# PV_power_board_0_1.net
KiCad netlist of a schematic drawn in EAGLE
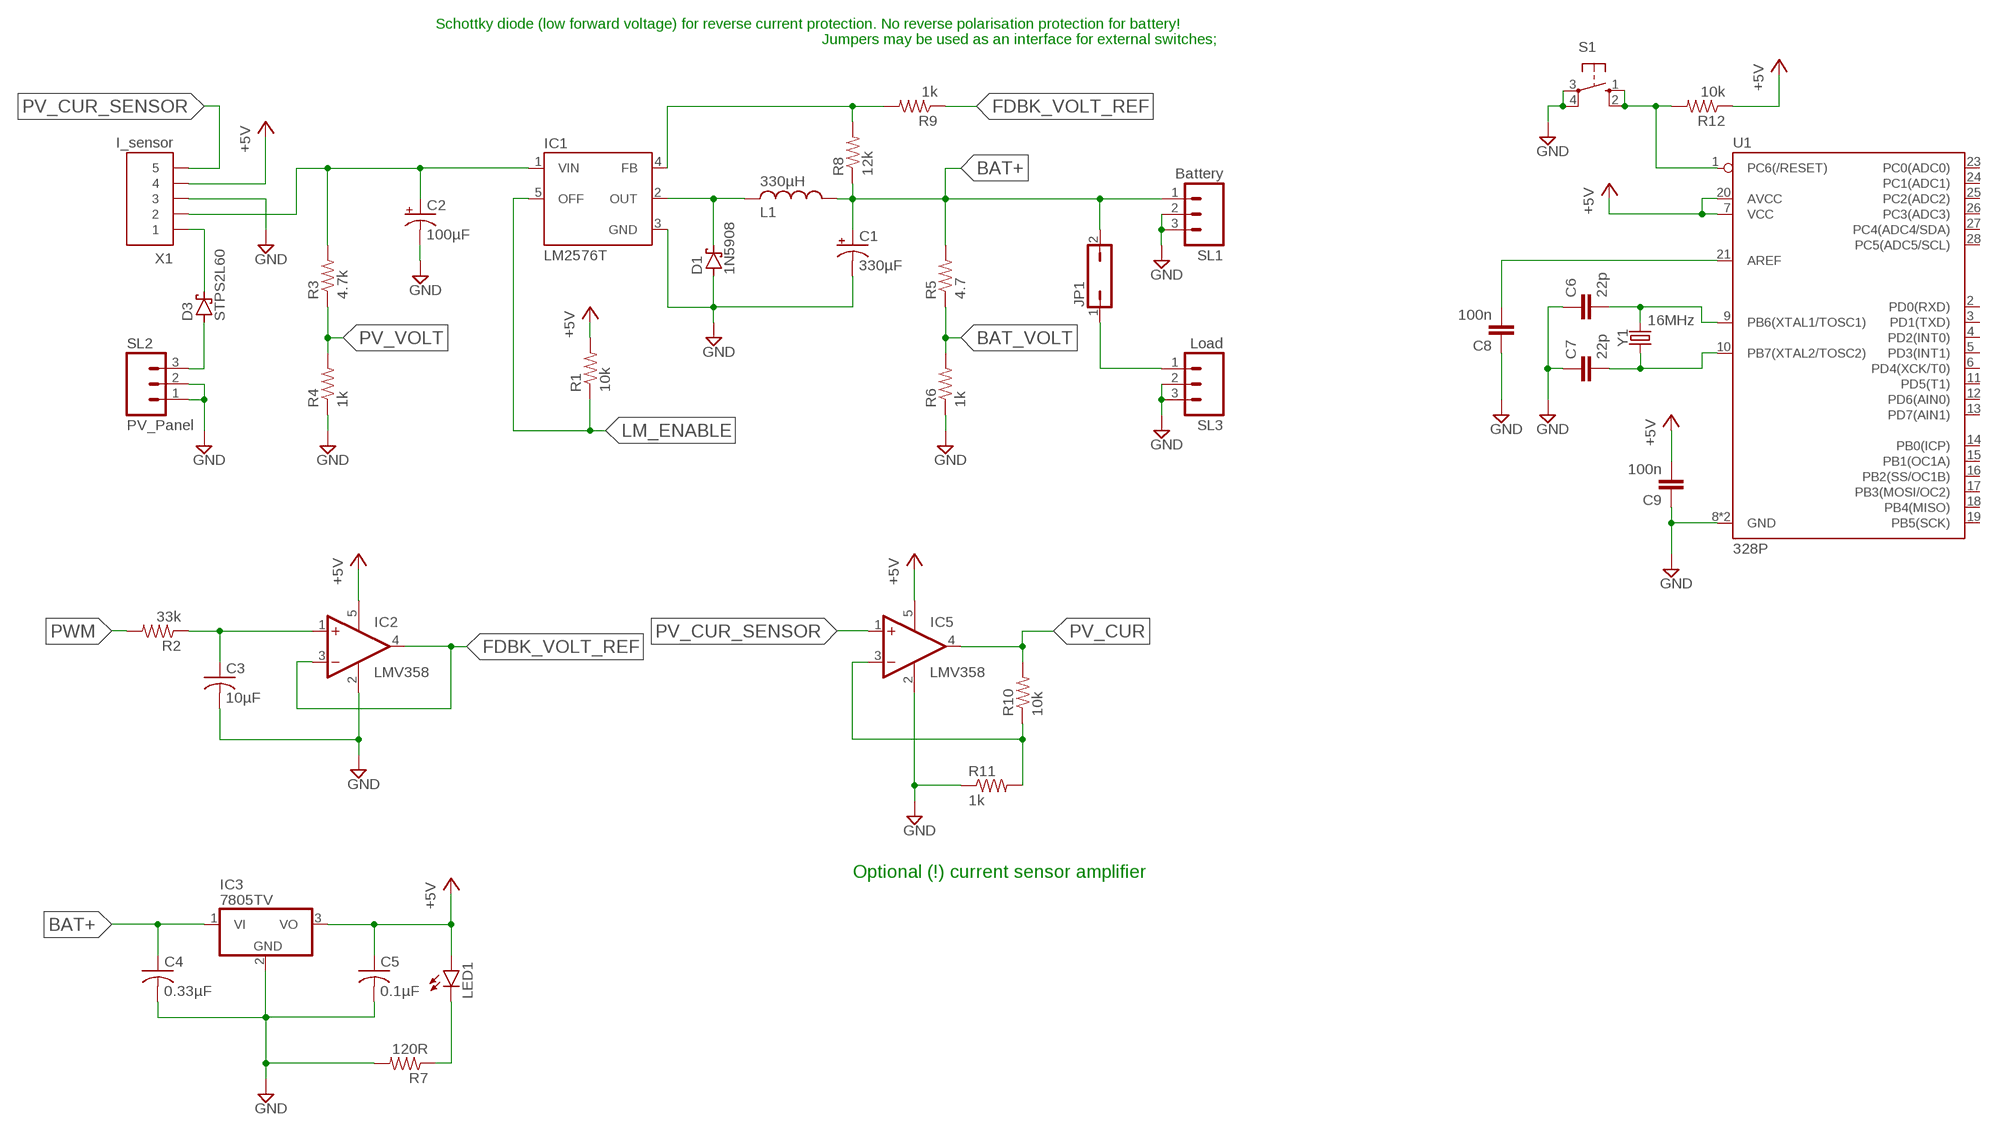
[diagram p0: schematic, sheet 1]

(export (version "E")
  (design (tool "Eeschema 10.0.6"))
  (components
    (comp (ref "C1")
      (value "330µF")
      (footprint "eagle-import:E3,5-8")
      (libsource (lib "eagle-import") (part "CPOL-USE3.5-8"))
    )
    (comp (ref "C2")
      (value "100µF")
      (footprint "eagle-import:E3,5-8")
      (libsource (lib "eagle-import") (part "CPOL-USE3.5-8"))
    )
    (comp (ref "C3")
      (value "10µF")
      (footprint "eagle-import:C025-025X050")
      (libsource (lib "eagle-import") (part "C-US025-025X050"))
    )
    (comp (ref "C4")
      (value "0.33µF")
      (footprint "eagle-import:C025-025X050")
      (libsource (lib "eagle-import") (part "C-US025-025X050"))
    )
    (comp (ref "C5")
      (value "0.1µF")
      (footprint "eagle-import:C025-025X050")
      (libsource (lib "eagle-import") (part "C-US025-025X050"))
    )
    (comp (ref "C6")
      (value "22p")
      (footprint "eagle-import:C2.5-2")
      (libsource (lib "eagle-import") (part "C2.5/2"))
    )
    (comp (ref "C7")
      (value "22p")
      (footprint "eagle-import:C2.5-2")
      (libsource (lib "eagle-import") (part "C2.5/2"))
    )
    (comp (ref "C8")
      (value "100n")
      (footprint "eagle-import:C2.5-2")
      (libsource (lib "eagle-import") (part "C2.5/2"))
    )
    (comp (ref "C9")
      (value "100n")
      (footprint "eagle-import:C2.5-2")
      (libsource (lib "eagle-import") (part "C2.5/2"))
    )
    (comp (ref "D1")
      (value "1N5908")
      (footprint "eagle-import:C4111-15")
      (libsource (lib "eagle-import") (part "1N5908"))
    )
    (comp (ref "D3")
      (value "STPS2L60")
      (footprint "eagle-import:C4111-15")
      (libsource (lib "eagle-import") (part "1N5908"))
    )
    (comp (ref "IC1")
      (value "LM2576T")
      (footprint "eagle-import:TO220-5")
      (libsource (lib "eagle-import") (part "LM2576T"))
    )
    (comp (ref "IC2")
      (value "LMV358")
      (footprint "eagle-import:SOT23-5")
      (libsource (lib "eagle-import") (part "LMV321?M5"))
    )
    (comp (ref "IC3")
      (value "7805TV")
      (footprint "eagle-import:TO220V")
      (libsource (lib "eagle-import") (part "78TV05"))
    )
    (comp (ref "IC5")
      (value "LMV358")
      (footprint "eagle-import:SOT23-5")
      (libsource (lib "eagle-import") (part "LMV321?M5"))
    )
    (comp (ref "JP1")
      (value "JP1Q")
      (footprint "eagle-import:JP1")
      (libsource (lib "eagle-import") (part "JP1Q"))
    )
    (comp (ref "L1")
      (value "330µH")
      (footprint "eagle-import:6000-XXXX-RC")
      (libsource (lib "eagle-import") (part "L-US6000-XXX-RC"))
    )
    (comp (ref "LED1")
      (value "LED5MM")
      (footprint "eagle-import:LED5MM")
      (libsource (lib "eagle-import") (part "LED5MM"))
    )
    (comp (ref "R1")
      (value "10k")
      (footprint "eagle-import:0207_10")
      (libsource (lib "eagle-import") (part "R-US_0207/10"))
    )
    (comp (ref "R2")
      (value "33k")
      (footprint "eagle-import:0207_10")
      (libsource (lib "eagle-import") (part "R-US_0207/10"))
    )
    (comp (ref "R3")
      (value "4.7k")
      (footprint "eagle-import:0207_10")
      (libsource (lib "eagle-import") (part "R-US_0207/10"))
    )
    (comp (ref "R4")
      (value "1k")
      (footprint "eagle-import:0207_10")
      (libsource (lib "eagle-import") (part "R-US_0207/10"))
    )
    (comp (ref "R5")
      (value "4.7")
      (footprint "eagle-import:0207_10")
      (libsource (lib "eagle-import") (part "R-US_0207/10"))
    )
    (comp (ref "R6")
      (value "1k")
      (footprint "eagle-import:0207_10")
      (libsource (lib "eagle-import") (part "R-US_0207/10"))
    )
    (comp (ref "R7")
      (value "120R")
      (footprint "eagle-import:0207_10")
      (libsource (lib "eagle-import") (part "R-US_0207/10"))
    )
    (comp (ref "R8")
      (value "12k")
      (footprint "eagle-import:0207_10")
      (libsource (lib "eagle-import") (part "R-US_0207/10"))
    )
    (comp (ref "R9")
      (value "1k")
      (footprint "eagle-import:0207_10")
      (libsource (lib "eagle-import") (part "R-US_0207/10"))
    )
    (comp (ref "R10")
      (value "10k")
      (footprint "eagle-import:0207_10")
      (libsource (lib "eagle-import") (part "R-US_0207/10"))
    )
    (comp (ref "R11")
      (value "1k")
      (footprint "eagle-import:0207_10")
      (libsource (lib "eagle-import") (part "R-US_0207/10"))
    )
    (comp (ref "R12")
      (value "10k")
      (footprint "eagle-import:0207_10")
      (libsource (lib "eagle-import") (part "R-US_0207/10"))
    )
    (comp (ref "S1")
      (value "10-XX")
      (footprint "eagle-import:B3F-10XX")
      (fields (field (name "MPN") "B3F-1000"))
      (libsource (lib "eagle-import") (part "10-XX"))
    )
    (comp (ref "SL1")
      (value "Battery")
      (footprint "eagle-import:03P")
      (libsource (lib "eagle-import") (part "M03"))
    )
    (comp (ref "SL2")
      (value "PV_Panel")
      (footprint "eagle-import:03P")
      (libsource (lib "eagle-import") (part "M03"))
    )
    (comp (ref "SL3")
      (value "Load")
      (footprint "eagle-import:03P")
      (libsource (lib "eagle-import") (part "M03"))
    )
    (comp (ref "U1")
      (value "328P")
      (footprint "eagle-import:DIP28")
      (libsource (lib "eagle-import") (part "ATMEGA328P_PDIP"))
    )
    (comp (ref "X1")
      (value "I_sensor")
      (footprint "eagle-import:MKS1855-6-0-505")
      (libsource (lib "eagle-import") (part "MKS1855-6-0-505"))
    )
    (comp (ref "Y1")
      (value "16MHz")
      (footprint "eagle-import:HC49US")
      (libsource (lib "eagle-import") (part "CRYSTAL-16MHZPTH-HC49US"))
    )
  )
  (nets
    (net (code "1") (name "+5V") (class "Default")
      (node (ref "C5") (pin "1") (pinfunction "1_1") (pintype "passive"))
      (node (ref "C9") (pin "2") (pinfunction "2_2") (pintype "passive"))
      (node (ref "IC2") (pin "5") (pinfunction "V+_5") (pintype "power_in"))
      (node (ref "IC3") (pin "3") (pinfunction "VO_3") (pintype "passive"))
      (node (ref "IC5") (pin "5") (pinfunction "V+_5") (pintype "power_in"))
      (node (ref "LED1") (pin "A") (pinfunction "A_A") (pintype "passive"))
      (node (ref "R1") (pin "2") (pinfunction "2_2") (pintype "passive"))
      (node (ref "R12") (pin "1") (pinfunction "1_1") (pintype "passive"))
      (node (ref "U1") (pin "20") (pinfunction "AVCC_20") (pintype "bidirectional"))
      (node (ref "U1") (pin "7") (pinfunction "VCC_7") (pintype "bidirectional"))
      (node (ref "X1") (pin "4") (pinfunction "4_4") (pintype "input"))
    )
    (net (code "2") (name "BAT+") (class "Default")
      (node (ref "C1") (pin "+") (pinfunction "+_+") (pintype "passive"))
      (node (ref "C4") (pin "1") (pinfunction "1_1") (pintype "passive"))
      (node (ref "IC3") (pin "1") (pinfunction "VI_1") (pintype "input"))
      (node (ref "JP1") (pin "2") (pinfunction "2_2") (pintype "passive"))
      (node (ref "L1") (pin "1") (pinfunction "1_1") (pintype "passive"))
      (node (ref "R5") (pin "2") (pinfunction "2_2") (pintype "passive"))
      (node (ref "R8") (pin "1") (pinfunction "1_1") (pintype "passive"))
      (node (ref "SL1") (pin "1") (pinfunction "1_1") (pintype "passive"))
    )
    (net (code "3") (name "BAT_VOLT") (class "Default")
      (node (ref "R5") (pin "1") (pinfunction "1_1") (pintype "passive"))
      (node (ref "R6") (pin "2") (pinfunction "2_2") (pintype "passive"))
    )
    (net (code "4") (name "FDBK_VOLT_REF") (class "Default")
      (node (ref "IC2") (pin "3") (pinfunction "-IN_3") (pintype "input"))
      (node (ref "IC2") (pin "4") (pinfunction "OUT_4") (pintype "output"))
      (node (ref "R9") (pin "1") (pinfunction "1_1") (pintype "passive"))
    )
    (net (code "5") (name "GND") (class "Default")
      (node (ref "C1") (pin "-") (pinfunction "-_-") (pintype "passive"))
      (node (ref "C2") (pin "-") (pinfunction "-_-") (pintype "passive"))
      (node (ref "C3") (pin "2") (pinfunction "2_2") (pintype "passive"))
      (node (ref "C4") (pin "2") (pinfunction "2_2") (pintype "passive"))
      (node (ref "C5") (pin "2") (pinfunction "2_2") (pintype "passive"))
      (node (ref "C6") (pin "1") (pinfunction "1_1") (pintype "passive"))
      (node (ref "C7") (pin "1") (pinfunction "1_1") (pintype "passive"))
      (node (ref "C8") (pin "1") (pinfunction "1_1") (pintype "passive"))
      (node (ref "C9") (pin "1") (pinfunction "1_1") (pintype "passive"))
      (node (ref "D1") (pin "A") (pinfunction "A_A") (pintype "passive"))
      (node (ref "IC1") (pin "3") (pinfunction "GND_3") (pintype "power_in"))
      (node (ref "IC2") (pin "2") (pinfunction "V-_2") (pintype "power_in"))
      (node (ref "IC3") (pin "2") (pinfunction "GND_2") (pintype "passive"))
      (node (ref "IC5") (pin "2") (pinfunction "V-_2") (pintype "power_in"))
      (node (ref "R11") (pin "1") (pinfunction "1_1") (pintype "passive"))
      (node (ref "R4") (pin "1") (pinfunction "1_1") (pintype "passive"))
      (node (ref "R6") (pin "1") (pinfunction "1_1") (pintype "passive"))
      (node (ref "R7") (pin "2") (pinfunction "2_2") (pintype "passive"))
      (node (ref "S1") (pin "3") (pinfunction "P_3") (pintype "passive"))
      (node (ref "S1") (pin "4") (pinfunction "P1_4") (pintype "passive"))
      (node (ref "SL1") (pin "2") (pinfunction "2_2") (pintype "passive"))
      (node (ref "SL1") (pin "3") (pinfunction "3_3") (pintype "passive"))
      (node (ref "SL2") (pin "1") (pinfunction "1_1") (pintype "passive"))
      (node (ref "SL2") (pin "2") (pinfunction "2_2") (pintype "passive"))
      (node (ref "SL3") (pin "2") (pinfunction "2_2") (pintype "passive"))
      (node (ref "SL3") (pin "3") (pinfunction "3_3") (pintype "passive"))
      (node (ref "U1") (pin "22") (pinfunction "GND_22") (pintype "bidirectional"))
      (node (ref "U1") (pin "8") (pinfunction "GND_8") (pintype "bidirectional"))
      (node (ref "X1") (pin "3") (pinfunction "3_3") (pintype "input"))
    )
    (net (code "6") (name "LM_ENABLE") (class "Default")
      (node (ref "IC1") (pin "5") (pinfunction "OFF_5") (pintype "input"))
      (node (ref "R1") (pin "1") (pinfunction "1_1") (pintype "passive"))
    )
    (net (code "7") (name "Net-(D3-PadA)") (class "Default")
      (node (ref "D3") (pin "A") (pinfunction "A_A") (pintype "passive"))
      (node (ref "SL2") (pin "3") (pinfunction "3_3") (pintype "passive"))
    )
    (net (code "8") (name "Net-(D3-PadC)") (class "Default")
      (node (ref "D3") (pin "C") (pinfunction "C_C") (pintype "passive"))
      (node (ref "X1") (pin "1") (pinfunction "1_1") (pintype "input"))
    )
    (net (code "9") (name "Net-(IC1-FB)") (class "Default")
      (node (ref "IC1") (pin "4") (pinfunction "FB_4") (pintype "input"))
      (node (ref "R8") (pin "2") (pinfunction "2_2") (pintype "passive"))
      (node (ref "R9") (pin "2") (pinfunction "2_2") (pintype "passive"))
    )
    (net (code "10") (name "Net-(IC1-OUT)") (class "Default")
      (node (ref "D1") (pin "C") (pinfunction "C_C") (pintype "passive"))
      (node (ref "IC1") (pin "2") (pinfunction "OUT_2") (pintype "output"))
      (node (ref "L1") (pin "2") (pinfunction "2_2") (pintype "passive"))
    )
    (net (code "11") (name "Net-(IC1-VIN)") (class "Default")
      (node (ref "C2") (pin "+") (pinfunction "+_+") (pintype "passive"))
      (node (ref "IC1") (pin "1") (pinfunction "VIN_1") (pintype "power_in"))
      (node (ref "R3") (pin "2") (pinfunction "2_2") (pintype "passive"))
      (node (ref "X1") (pin "2") (pinfunction "2_2") (pintype "input"))
    )
    (net (code "12") (name "Net-(IC2-+IN)") (class "Default")
      (node (ref "C3") (pin "1") (pinfunction "1_1") (pintype "passive"))
      (node (ref "IC2") (pin "1") (pinfunction "+IN_1") (pintype "input"))
      (node (ref "R2") (pin "1") (pinfunction "1_1") (pintype "passive"))
    )
    (net (code "13") (name "Net-(IC5--IN)") (class "Default")
      (node (ref "IC5") (pin "3") (pinfunction "-IN_3") (pintype "input"))
      (node (ref "R10") (pin "1") (pinfunction "1_1") (pintype "passive"))
      (node (ref "R11") (pin "2") (pinfunction "2_2") (pintype "passive"))
    )
    (net (code "14") (name "Net-(JP1-Pad1)") (class "Default")
      (node (ref "JP1") (pin "1") (pinfunction "1_1") (pintype "passive"))
      (node (ref "SL3") (pin "1") (pinfunction "1_1") (pintype "passive"))
    )
    (net (code "15") (name "Net-(LED1-C)") (class "Default")
      (node (ref "LED1") (pin "K") (pinfunction "C_K") (pintype "passive"))
      (node (ref "R7") (pin "1") (pinfunction "1_1") (pintype "passive"))
    )
    (net (code "16") (name "Net-(S1-S)") (class "Default")
      (node (ref "R12") (pin "2") (pinfunction "2_2") (pintype "passive"))
      (node (ref "S1") (pin "1") (pinfunction "S_1") (pintype "passive"))
      (node (ref "S1") (pin "2") (pinfunction "S1_2") (pintype "passive"))
      (node (ref "U1") (pin "1") (pinfunction "PC6(/RESET)_1") (pintype "bidirectional"))
    )
    (net (code "17") (name "Net-(U1-AREF)") (class "Default")
      (node (ref "C8") (pin "2") (pinfunction "2_2") (pintype "passive"))
      (node (ref "U1") (pin "21") (pinfunction "AREF_21") (pintype "bidirectional"))
    )
    (net (code "18") (name "Net-(U1-PB6(XTAL1{slash}TOSC1))") (class "Default")
      (node (ref "C6") (pin "2") (pinfunction "2_2") (pintype "passive"))
      (node (ref "U1") (pin "9") (pinfunction "PB6(XTAL1/TOSC1)_9") (pintype "bidirectional"))
      (node (ref "Y1") (pin "2") (pinfunction "2_2") (pintype "passive"))
    )
    (net (code "19") (name "Net-(U1-PB7(XTAL2{slash}TOSC2))") (class "Default")
      (node (ref "C7") (pin "2") (pinfunction "2_2") (pintype "passive"))
      (node (ref "U1") (pin "10") (pinfunction "PB7(XTAL2/TOSC2)_10") (pintype "bidirectional"))
      (node (ref "Y1") (pin "1") (pinfunction "1_1") (pintype "passive"))
    )
    (net (code "20") (name "PV_CUR") (class "Default")
      (node (ref "IC5") (pin "4") (pinfunction "OUT_4") (pintype "output"))
      (node (ref "R10") (pin "2") (pinfunction "2_2") (pintype "passive"))
    )
    (net (code "21") (name "PV_CUR_SENSOR") (class "Default")
      (node (ref "IC5") (pin "1") (pinfunction "+IN_1") (pintype "input"))
      (node (ref "X1") (pin "5") (pinfunction "5_5") (pintype "input"))
    )
    (net (code "22") (name "PV_VOLT") (class "Default")
      (node (ref "R3") (pin "1") (pinfunction "1_1") (pintype "passive"))
      (node (ref "R4") (pin "2") (pinfunction "2_2") (pintype "passive"))
    )
    (net (code "23") (name "PWM") (class "Default")
      (node (ref "R2") (pin "2") (pinfunction "2_2") (pintype "passive"))
    )
    (net (code "24") (name "unconnected-(U1-PB0(ICP)-Pad14)") (class "Default")
      (node (ref "U1") (pin "14") (pinfunction "PB0(ICP)_14") (pintype "bidirectional"))
    )
    (net (code "25") (name "unconnected-(U1-PB1(OC1A)-Pad15)") (class "Default")
      (node (ref "U1") (pin "15") (pinfunction "PB1(OC1A)_15") (pintype "bidirectional"))
    )
    (net (code "26") (name "unconnected-(U1-PB2(SS{slash}OC1B)-Pad16)") (class "Default")
      (node (ref "U1") (pin "16") (pinfunction "PB2(SS/OC1B)_16") (pintype "bidirectional"))
    )
    (net (code "27") (name "unconnected-(U1-PB3(MOSI{slash}OC2)-Pad17)") (class "Default")
      (node (ref "U1") (pin "17") (pinfunction "PB3(MOSI/OC2)_17") (pintype "bidirectional"))
    )
    (net (code "28") (name "unconnected-(U1-PB4(MISO)-Pad18)") (class "Default")
      (node (ref "U1") (pin "18") (pinfunction "PB4(MISO)_18") (pintype "bidirectional"))
    )
    (net (code "29") (name "unconnected-(U1-PB5(SCK)-Pad19)") (class "Default")
      (node (ref "U1") (pin "19") (pinfunction "PB5(SCK)_19") (pintype "bidirectional"))
    )
    (net (code "30") (name "unconnected-(U1-PC0(ADC0)-Pad23)") (class "Default")
      (node (ref "U1") (pin "23") (pinfunction "PC0(ADC0)_23") (pintype "bidirectional"))
    )
    (net (code "31") (name "unconnected-(U1-PC1(ADC1)-Pad24)") (class "Default")
      (node (ref "U1") (pin "24") (pinfunction "PC1(ADC1)_24") (pintype "bidirectional"))
    )
    (net (code "32") (name "unconnected-(U1-PC2(ADC2)-Pad25)") (class "Default")
      (node (ref "U1") (pin "25") (pinfunction "PC2(ADC2)_25") (pintype "bidirectional"))
    )
    (net (code "33") (name "unconnected-(U1-PC3(ADC3)-Pad26)") (class "Default")
      (node (ref "U1") (pin "26") (pinfunction "PC3(ADC3)_26") (pintype "bidirectional"))
    )
    (net (code "34") (name "unconnected-(U1-PC4(ADC4{slash}SDA)-Pad27)") (class "Default")
      (node (ref "U1") (pin "27") (pinfunction "PC4(ADC4/SDA)_27") (pintype "bidirectional"))
    )
    (net (code "35") (name "unconnected-(U1-PC5(ADC5{slash}SCL)-Pad28)") (class "Default")
      (node (ref "U1") (pin "28") (pinfunction "PC5(ADC5/SCL)_28") (pintype "bidirectional"))
    )
    (net (code "36") (name "unconnected-(U1-PD0(RXD)-Pad2)") (class "Default")
      (node (ref "U1") (pin "2") (pinfunction "PD0(RXD)_2") (pintype "bidirectional"))
    )
    (net (code "37") (name "unconnected-(U1-PD1(TXD)-Pad3)") (class "Default")
      (node (ref "U1") (pin "3") (pinfunction "PD1(TXD)_3") (pintype "bidirectional"))
    )
    (net (code "38") (name "unconnected-(U1-PD2(INT0)-Pad4)") (class "Default")
      (node (ref "U1") (pin "4") (pinfunction "PD2(INT0)_4") (pintype "bidirectional"))
    )
    (net (code "39") (name "unconnected-(U1-PD3(INT1)-Pad5)") (class "Default")
      (node (ref "U1") (pin "5") (pinfunction "PD3(INT1)_5") (pintype "bidirectional"))
    )
    (net (code "40") (name "unconnected-(U1-PD4(XCK{slash}T0)-Pad6)") (class "Default")
      (node (ref "U1") (pin "6") (pinfunction "PD4(XCK/T0)_6") (pintype "bidirectional"))
    )
    (net (code "41") (name "unconnected-(U1-PD5(T1)-Pad11)") (class "Default")
      (node (ref "U1") (pin "11") (pinfunction "PD5(T1)_11") (pintype "bidirectional"))
    )
    (net (code "42") (name "unconnected-(U1-PD6(AIN0)-Pad12)") (class "Default")
      (node (ref "U1") (pin "12") (pinfunction "PD6(AIN0)_12") (pintype "bidirectional"))
    )
    (net (code "43") (name "unconnected-(U1-PD7(AIN1)-Pad13)") (class "Default")
      (node (ref "U1") (pin "13") (pinfunction "PD7(AIN1)_13") (pintype "bidirectional"))
    )
  )
)
